# PCB_1_5V_To_3_3v_Regulator_project.net
KiCad netlist of a schematic drawn in Altium Designer
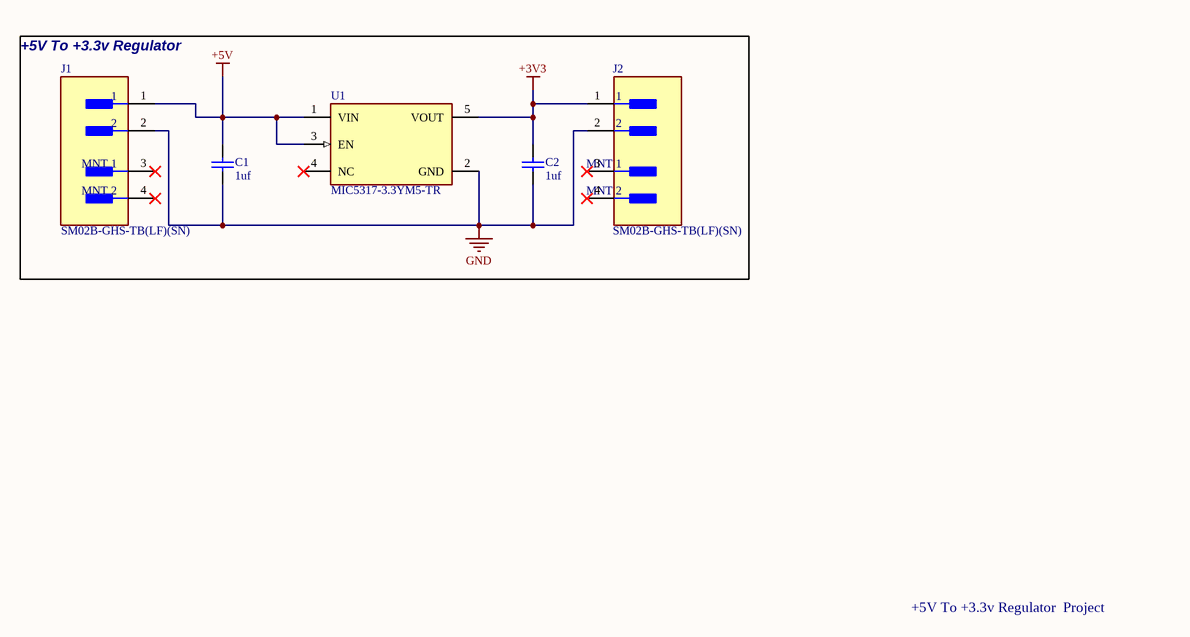
[diagram p0: PCB 1 +5V To +3.3v Regulator project.SchDoc]

(export (version "E")
  (design (tool "Eeschema 10.0.6"))
  (components
    (comp (ref "C1")
      (value "1uf")
      (footprint "CAPC2013X145X50NL20T20")
      (fields (field (name "PART NUMBER") "VJ0805Y105KXQRW1BC") (field (name "MANUFACTURER") "Vitramon"))
      (libsource (lib "Altium Content Vault") (part "CAP"))
    )
    (comp (ref "C2")
      (value "1uf")
      (footprint "CAPC2013X145X50NL20T20")
      (fields (field (name "PART NUMBER") "VJ0805Y105KXQRW1BC") (field (name "MANUFACTURER") "Vitramon"))
      (libsource (lib "Altium Content Vault") (part "CAP"))
    )
    (comp (ref "J1")
      (value "SM02B-GHS-TB(LF)(SN)")
      (footprint "FP-SM02B-GHS-TB_LF_SN-MFG")
      (description "CONN HEADER SMD R/A 2POS 1.25MM")
      (libsource (lib "") (part "56ec3178a87b3978bdc1b3682cd516a_1"))
    )
    (comp (ref "J2")
      (value "SM02B-GHS-TB(LF)(SN)")
      (footprint "FP-SM02B-GHS-TB_LF_SN-MFG")
      (description "CONN HEADER SMD R/A 2POS 1.25MM")
      (libsource (lib "Altium Content Vault") (part "56ec3178a87b3978bdc1b3682cd516a"))
    )
    (comp (ref "U1")
      (value "MIC5317-3.3YM5-TR")
      (footprint "FP-SOT23-5LD-PL-1-MFG")
      (description "IC REG LINEAR 3.3V 150MA SOT23-5")
      (libsource (lib "Altium Content Vault") (part "0a093dae7315cdc977fd108dde87457"))
    )
  )
  (nets
    (net (code "1") (name "+3V3") (class "Default")
      (node (ref "C2") (pin "2") (pinfunction "2_2") (pintype "passive"))
      (node (ref "J2") (pin "1") (pinfunction "1_1") (pintype "passive"))
      (node (ref "U1") (pin "5") (pinfunction "VOUT_5") (pintype "power_in"))
    )
    (net (code "2") (name "+5V") (class "Default")
      (node (ref "C1") (pin "2") (pinfunction "2_2") (pintype "passive"))
      (node (ref "J1") (pin "1") (pinfunction "1_1") (pintype "passive"))
      (node (ref "U1") (pin "1") (pinfunction "VIN_1") (pintype "power_in"))
      (node (ref "U1") (pin "3") (pinfunction "EN_3") (pintype "input"))
    )
    (net (code "3") (name "GND") (class "Default")
      (node (ref "C1") (pin "1") (pinfunction "1_1") (pintype "passive"))
      (node (ref "C2") (pin "1") (pinfunction "1_1") (pintype "passive"))
      (node (ref "J1") (pin "2") (pinfunction "2_2") (pintype "passive"))
      (node (ref "J2") (pin "2") (pinfunction "2_2") (pintype "passive"))
      (node (ref "U1") (pin "2") (pinfunction "GND_2") (pintype "power_in"))
    )
    (net (code "4") (name "unconnected-(J1-MNT_1-Pad3)") (class "Default")
      (node (ref "J1") (pin "3") (pinfunction "MNT_1_3") (pintype "passive+no_connect"))
    )
    (net (code "5") (name "unconnected-(J1-MNT_2-Pad4)") (class "Default")
      (node (ref "J1") (pin "4") (pinfunction "MNT_2_4") (pintype "passive+no_connect"))
    )
    (net (code "6") (name "unconnected-(J2-MNT_1-Pad3)") (class "Default")
      (node (ref "J2") (pin "3") (pinfunction "MNT_1_3") (pintype "passive+no_connect"))
    )
    (net (code "7") (name "unconnected-(J2-MNT_2-Pad4)") (class "Default")
      (node (ref "J2") (pin "4") (pinfunction "MNT_2_4") (pintype "passive+no_connect"))
    )
    (net (code "8") (name "unconnected-(U1-NC-Pad4)") (class "Default")
      (node (ref "U1") (pin "4") (pinfunction "NC_4") (pintype "passive+no_connect"))
    )
  )
)
